# 17_FPGA_B12_B13_B14_B15.net
KiCad netlist of a schematic drawn in Altium Designer
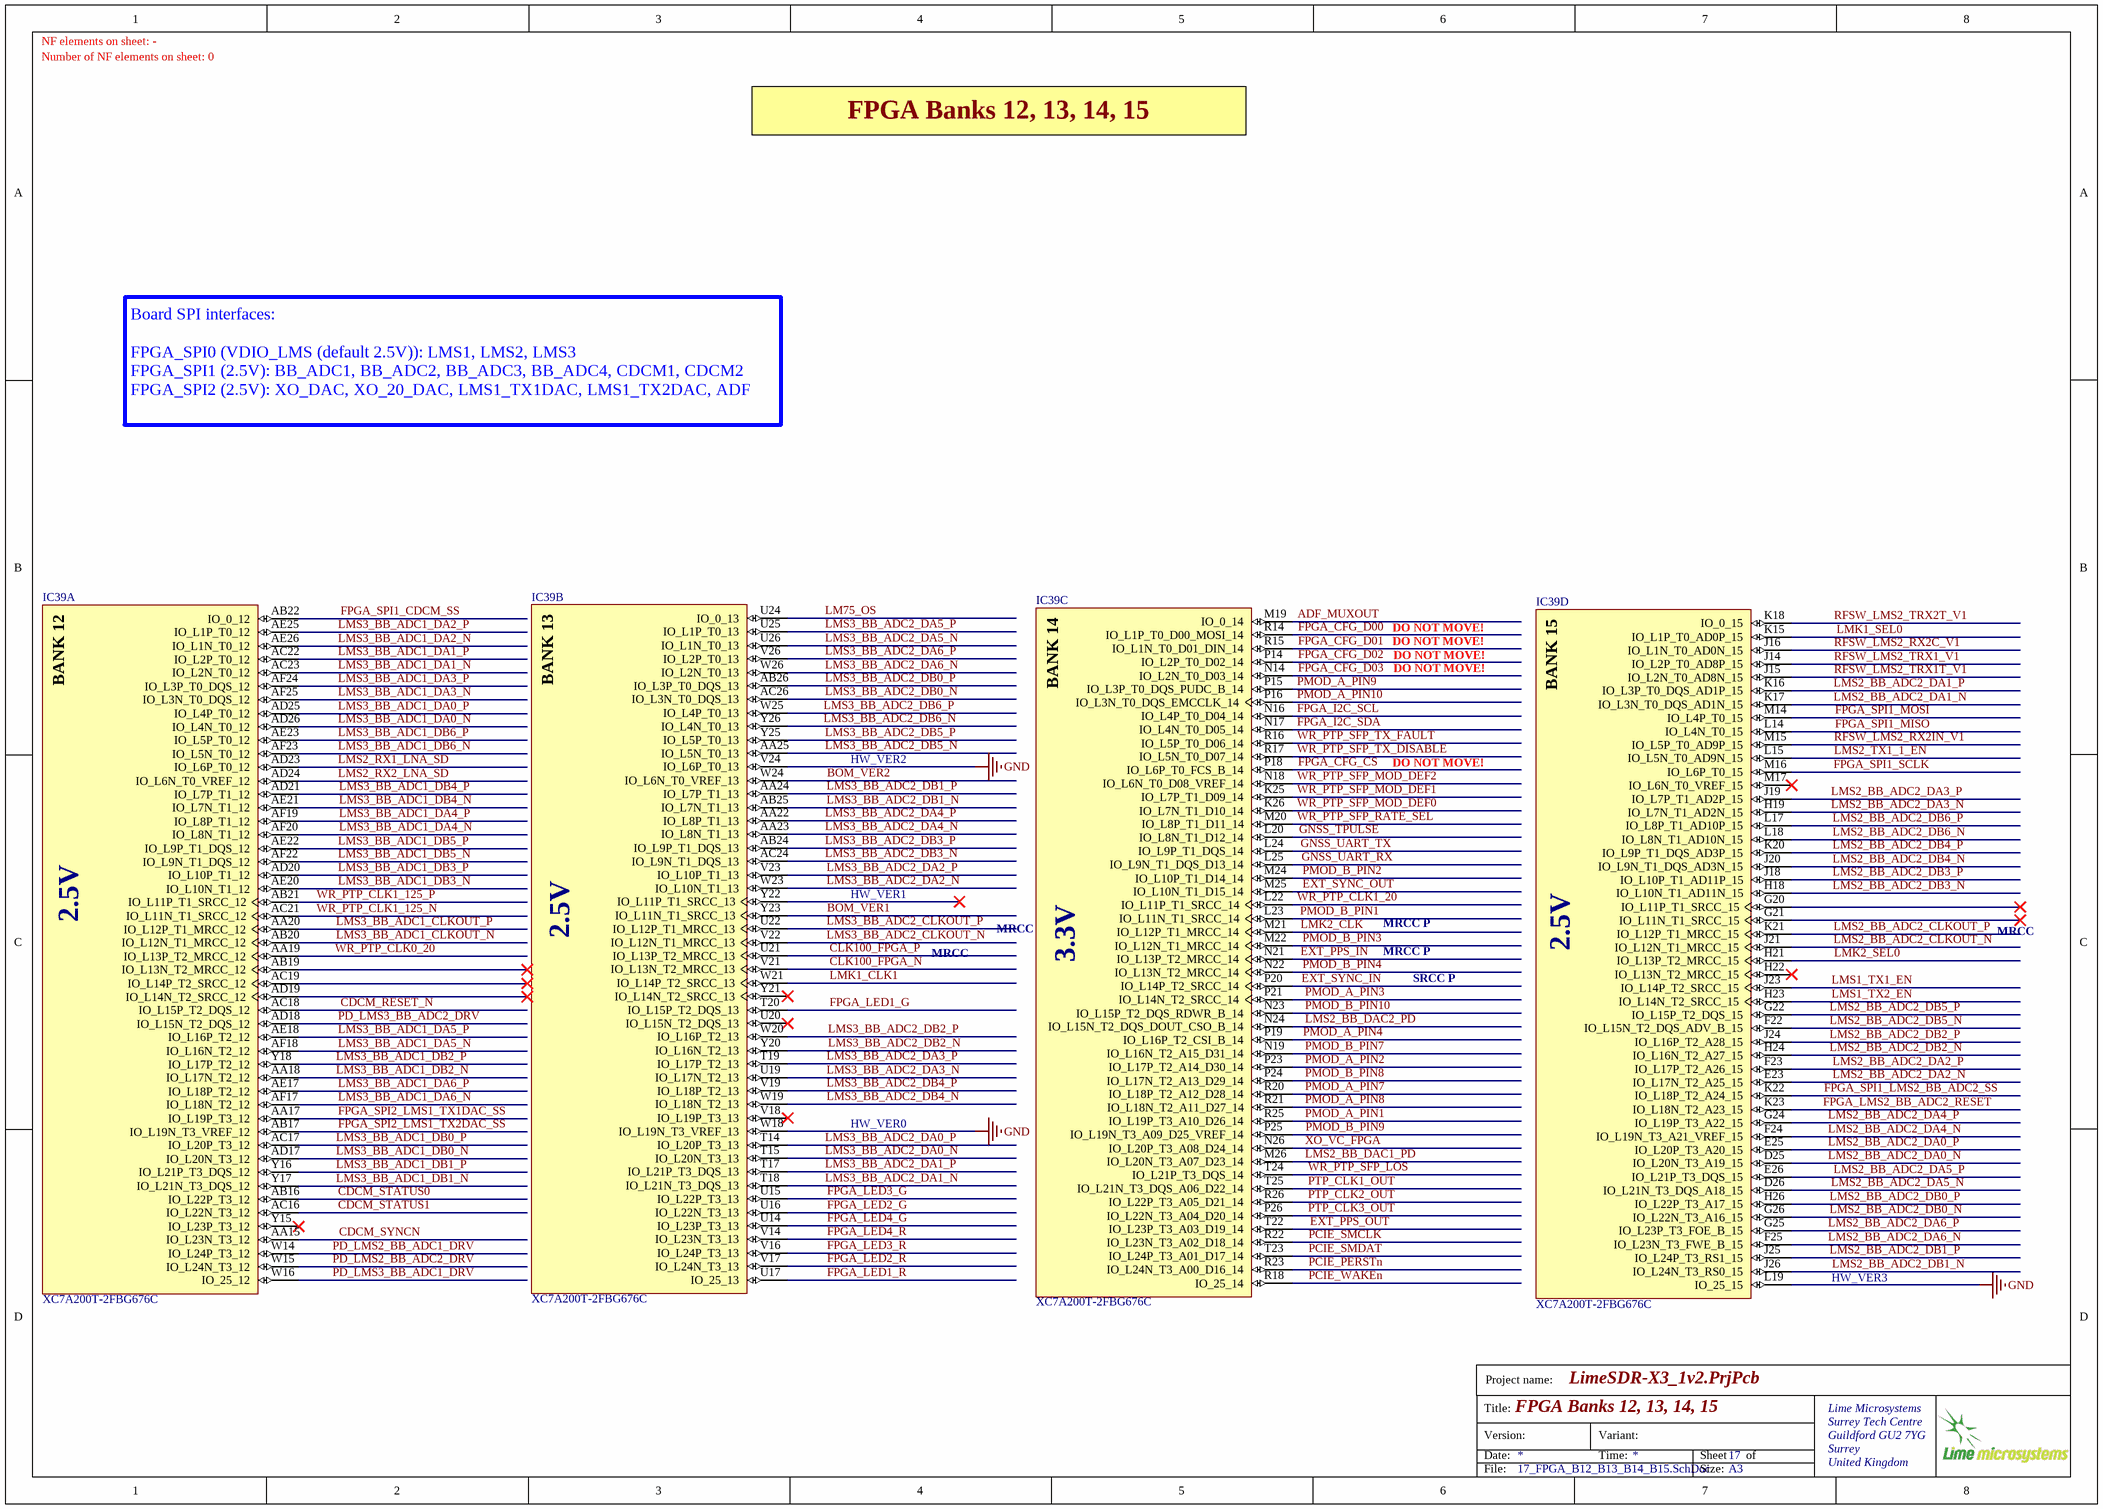
[diagram p0: 17_FPGA_B12_B13_B14_B15.SchDoc]

(export (version "E")
  (design (tool "Eeschema 10.0.6"))
  (components
    (comp (ref "IC39")
      (value "XC7A200T-2FBG676C")
      (footprint "XC7A200T-2FBG676C_FBG676")
      (description "Artix-7 FPGA, 400 User I/Os, 8 GTP, 676-Ball BGA, Speed Grade 2, Commercial Grade, Pb-Free")
      (fields (field (name "MANUFACTURER") "Xilinx"))
      (libsource (lib "") (part "XC7A200T-2FBG676C_3"))
    )
  )
  (nets
    (net (code "1") (name "/ADF_MUXOUT") (class "Default")
      (node (ref "IC39") (pin "M19") (pinfunction "IO_0_14_M19") (pintype "bidirectional"))
    )
    (net (code "2") (name "/BOM_VER1") (class "Default")
      (node (ref "IC39") (pin "Y23") (pinfunction "IO_L11N_T1_SRCC_13_Y23") (pintype "bidirectional"))
    )
    (net (code "3") (name "/BOM_VER2") (class "Default")
      (node (ref "IC39") (pin "W24") (pinfunction "IO_L6N_T0_VREF_13_W24") (pintype "bidirectional"))
    )
    (net (code "4") (name "/CDCM_RESET_N") (class "Default")
      (node (ref "IC39") (pin "AC18") (pinfunction "IO_L15P_T2_DQS_12_AC18") (pintype "bidirectional"))
    )
    (net (code "5") (name "/CDCM_STATUS0") (class "Default")
      (node (ref "IC39") (pin "AB16") (pinfunction "IO_L22P_T3_12_AB16") (pintype "bidirectional"))
    )
    (net (code "6") (name "/CDCM_STATUS1") (class "Default")
      (node (ref "IC39") (pin "AC16") (pinfunction "IO_L22N_T3_12_AC16") (pintype "bidirectional"))
    )
    (net (code "7") (name "/CDCM_SYNCN") (class "Default")
      (node (ref "IC39") (pin "AA15") (pinfunction "IO_L23N_T3_12_AA15") (pintype "bidirectional"))
    )
    (net (code "8") (name "/CLK100_FPGA_N") (class "Default")
      (node (ref "IC39") (pin "V21") (pinfunction "IO_L13N_T2_MRCC_13_V21") (pintype "bidirectional"))
    )
    (net (code "9") (name "/CLK100_FPGA_P") (class "Default")
      (node (ref "IC39") (pin "U21") (pinfunction "IO_L13P_T2_MRCC_13_U21") (pintype "bidirectional"))
    )
    (net (code "10") (name "/EXT_PPS_IN") (class "Default")
      (node (ref "IC39") (pin "N21") (pinfunction "IO_L13P_T2_MRCC_14_N21") (pintype "bidirectional"))
    )
    (net (code "11") (name "/EXT_PPS_OUT") (class "Default")
      (node (ref "IC39") (pin "T22") (pinfunction "IO_L23P_T3_A03_D19_14_T22") (pintype "bidirectional"))
    )
    (net (code "12") (name "/EXT_SYNC_IN") (class "Default")
      (node (ref "IC39") (pin "P20") (pinfunction "IO_L14P_T2_SRCC_14_P20") (pintype "bidirectional"))
    )
    (net (code "13") (name "/EXT_SYNC_OUT") (class "Default")
      (node (ref "IC39") (pin "M25") (pinfunction "IO_L10N_T1_D15_14_M25") (pintype "bidirectional"))
    )
    (net (code "14") (name "/FPGA_CFG_CS") (class "Default")
      (node (ref "IC39") (pin "P18") (pinfunction "IO_L6P_T0_FCS_B_14_P18") (pintype "bidirectional"))
    )
    (net (code "15") (name "/FPGA_CFG_D00") (class "Default")
      (node (ref "IC39") (pin "R14") (pinfunction "IO_L1P_T0_D00_MOSI_14_R14") (pintype "bidirectional"))
    )
    (net (code "16") (name "/FPGA_CFG_D01") (class "Default")
      (node (ref "IC39") (pin "R15") (pinfunction "IO_L1N_T0_D01_DIN_14_R15") (pintype "bidirectional"))
    )
    (net (code "17") (name "/FPGA_CFG_D02") (class "Default")
      (node (ref "IC39") (pin "P14") (pinfunction "IO_L2P_T0_D02_14_P14") (pintype "bidirectional"))
    )
    (net (code "18") (name "/FPGA_CFG_D03") (class "Default")
      (node (ref "IC39") (pin "N14") (pinfunction "IO_L2N_T0_D03_14_N14") (pintype "bidirectional"))
    )
    (net (code "19") (name "/FPGA_I2C_SCL") (class "Default")
      (node (ref "IC39") (pin "N16") (pinfunction "IO_L4P_T0_D04_14_N16") (pintype "bidirectional"))
    )
    (net (code "20") (name "/FPGA_I2C_SDA") (class "Default")
      (node (ref "IC39") (pin "N17") (pinfunction "IO_L4N_T0_D05_14_N17") (pintype "bidirectional"))
    )
    (net (code "21") (name "/FPGA_LED1_G") (class "Default")
      (node (ref "IC39") (pin "T20") (pinfunction "IO_L15P_T2_DQS_13_T20") (pintype "bidirectional"))
    )
    (net (code "22") (name "/FPGA_LED1_R") (class "Default")
      (node (ref "IC39") (pin "U17") (pinfunction "IO_25_13_U17") (pintype "bidirectional"))
    )
    (net (code "23") (name "/FPGA_LED2_G") (class "Default")
      (node (ref "IC39") (pin "U16") (pinfunction "IO_L22N_T3_13_U16") (pintype "bidirectional"))
    )
    (net (code "24") (name "/FPGA_LED2_R") (class "Default")
      (node (ref "IC39") (pin "V17") (pinfunction "IO_L24N_T3_13_V17") (pintype "bidirectional"))
    )
    (net (code "25") (name "/FPGA_LED3_G") (class "Default")
      (node (ref "IC39") (pin "U15") (pinfunction "IO_L22P_T3_13_U15") (pintype "bidirectional"))
    )
    (net (code "26") (name "/FPGA_LED3_R") (class "Default")
      (node (ref "IC39") (pin "V16") (pinfunction "IO_L24P_T3_13_V16") (pintype "bidirectional"))
    )
    (net (code "27") (name "/FPGA_LED4_G") (class "Default")
      (node (ref "IC39") (pin "U14") (pinfunction "IO_L23P_T3_13_U14") (pintype "bidirectional"))
    )
    (net (code "28") (name "/FPGA_LED4_R") (class "Default")
      (node (ref "IC39") (pin "V14") (pinfunction "IO_L23N_T3_13_V14") (pintype "bidirectional"))
    )
    (net (code "29") (name "/FPGA_LMS2_BB_ADC2_RESET") (class "Default")
      (node (ref "IC39") (pin "K23") (pinfunction "IO_L18N_T2_A23_15_K23") (pintype "bidirectional"))
    )
    (net (code "30") (name "/FPGA_SPI1_CDCM_SS") (class "Default")
      (node (ref "IC39") (pin "AB22") (pinfunction "IO_0_12_AB22") (pintype "bidirectional"))
    )
    (net (code "31") (name "/FPGA_SPI1_LMS2_BB_ADC2_SS") (class "Default")
      (node (ref "IC39") (pin "K22") (pinfunction "IO_L18P_T2_A24_15_K22") (pintype "bidirectional"))
    )
    (net (code "32") (name "/FPGA_SPI1_MISO") (class "Default")
      (node (ref "IC39") (pin "L14") (pinfunction "IO_L4N_T0_15_L14") (pintype "bidirectional"))
    )
    (net (code "33") (name "/FPGA_SPI1_MOSI") (class "Default")
      (node (ref "IC39") (pin "M14") (pinfunction "IO_L4P_T0_15_M14") (pintype "bidirectional"))
    )
    (net (code "34") (name "/FPGA_SPI1_SCLK") (class "Default")
      (node (ref "IC39") (pin "M16") (pinfunction "IO_L6P_T0_15_M16") (pintype "bidirectional"))
    )
    (net (code "35") (name "/FPGA_SPI2_LMS1_TX1DAC_SS") (class "Default")
      (node (ref "IC39") (pin "AA17") (pinfunction "IO_L19P_T3_12_AA17") (pintype "bidirectional"))
    )
    (net (code "36") (name "/FPGA_SPI2_LMS1_TX2DAC_SS") (class "Default")
      (node (ref "IC39") (pin "AB17") (pinfunction "IO_L19N_T3_VREF_12_AB17") (pintype "bidirectional"))
    )
    (net (code "37") (name "/GNSS_TPULSE") (class "Default")
      (node (ref "IC39") (pin "L20") (pinfunction "IO_L8N_T1_D12_14_L20") (pintype "bidirectional"))
    )
    (net (code "38") (name "/GNSS_UART_RX") (class "Default")
      (node (ref "IC39") (pin "L25") (pinfunction "IO_L9N_T1_DQS_D13_14_L25") (pintype "bidirectional"))
    )
    (net (code "39") (name "/GNSS_UART_TX") (class "Default")
      (node (ref "IC39") (pin "L24") (pinfunction "IO_L9P_T1_DQS_14_L24") (pintype "bidirectional"))
    )
    (net (code "40") (name "/LM75_OS") (class "Default")
      (node (ref "IC39") (pin "U24") (pinfunction "IO_0_13_U24") (pintype "bidirectional"))
    )
    (net (code "41") (name "/LMK1_CLK1") (class "Default")
      (node (ref "IC39") (pin "W21") (pinfunction "IO_L14P_T2_SRCC_13_W21") (pintype "bidirectional"))
    )
    (net (code "42") (name "/LMK1_SEL0") (class "Default")
      (node (ref "IC39") (pin "K15") (pinfunction "IO_L1P_T0_AD0P_15_K15") (pintype "bidirectional"))
    )
    (net (code "43") (name "/LMK2_CLK") (class "Default")
      (node (ref "IC39") (pin "M21") (pinfunction "IO_L12P_T1_MRCC_14_M21") (pintype "bidirectional"))
    )
    (net (code "44") (name "/LMK2_SEL0") (class "Default")
      (node (ref "IC39") (pin "H21") (pinfunction "IO_L13P_T2_MRCC_15_H21") (pintype "bidirectional"))
    )
    (net (code "45") (name "/LMS1_TX1_EN") (class "Default")
      (node (ref "IC39") (pin "J23") (pinfunction "IO_L14P_T2_SRCC_15_J23") (pintype "bidirectional"))
    )
    (net (code "46") (name "/LMS1_TX2_EN") (class "Default")
      (node (ref "IC39") (pin "H23") (pinfunction "IO_L14N_T2_SRCC_15_H23") (pintype "bidirectional"))
    )
    (net (code "47") (name "/LMS2_BB_ADC2_CLKOUT_N") (class "Default")
      (node (ref "IC39") (pin "J21") (pinfunction "IO_L12N_T1_MRCC_15_J21") (pintype "bidirectional"))
    )
    (net (code "48") (name "/LMS2_BB_ADC2_CLKOUT_P") (class "Default")
      (node (ref "IC39") (pin "K21") (pinfunction "IO_L12P_T1_MRCC_15_K21") (pintype "bidirectional"))
    )
    (net (code "49") (name "/LMS2_BB_ADC2_DA0_N") (class "Default")
      (node (ref "IC39") (pin "D25") (pinfunction "IO_L20N_T3_A19_15_D25") (pintype "bidirectional"))
    )
    (net (code "50") (name "/LMS2_BB_ADC2_DA0_P") (class "Default")
      (node (ref "IC39") (pin "E25") (pinfunction "IO_L20P_T3_A20_15_E25") (pintype "bidirectional"))
    )
    (net (code "51") (name "/LMS2_BB_ADC2_DA1_N") (class "Default")
      (node (ref "IC39") (pin "K17") (pinfunction "IO_L3N_T0_DQS_AD1N_15_K17") (pintype "bidirectional"))
    )
    (net (code "52") (name "/LMS2_BB_ADC2_DA1_P") (class "Default")
      (node (ref "IC39") (pin "K16") (pinfunction "IO_L3P_T0_DQS_AD1P_15_K16") (pintype "bidirectional"))
    )
    (net (code "53") (name "/LMS2_BB_ADC2_DA2_N") (class "Default")
      (node (ref "IC39") (pin "E23") (pinfunction "IO_L17N_T2_A25_15_E23") (pintype "bidirectional"))
    )
    (net (code "54") (name "/LMS2_BB_ADC2_DA2_P") (class "Default")
      (node (ref "IC39") (pin "F23") (pinfunction "IO_L17P_T2_A26_15_F23") (pintype "bidirectional"))
    )
    (net (code "55") (name "/LMS2_BB_ADC2_DA3_N") (class "Default")
      (node (ref "IC39") (pin "H19") (pinfunction "IO_L7N_T1_AD2N_15_H19") (pintype "bidirectional"))
    )
    (net (code "56") (name "/LMS2_BB_ADC2_DA3_P") (class "Default")
      (node (ref "IC39") (pin "J19") (pinfunction "IO_L7P_T1_AD2P_15_J19") (pintype "bidirectional"))
    )
    (net (code "57") (name "/LMS2_BB_ADC2_DA4_N") (class "Default")
      (node (ref "IC39") (pin "F24") (pinfunction "IO_L19N_T3_A21_VREF_15_F24") (pintype "bidirectional"))
    )
    (net (code "58") (name "/LMS2_BB_ADC2_DA4_P") (class "Default")
      (node (ref "IC39") (pin "G24") (pinfunction "IO_L19P_T3_A22_15_G24") (pintype "bidirectional"))
    )
    (net (code "59") (name "/LMS2_BB_ADC2_DA5_N") (class "Default")
      (node (ref "IC39") (pin "D26") (pinfunction "IO_L21N_T3_DQS_A18_15_D26") (pintype "bidirectional"))
    )
    (net (code "60") (name "/LMS2_BB_ADC2_DA5_P") (class "Default")
      (node (ref "IC39") (pin "E26") (pinfunction "IO_L21P_T3_DQS_15_E26") (pintype "bidirectional"))
    )
    (net (code "61") (name "/LMS2_BB_ADC2_DA6_N") (class "Default")
      (node (ref "IC39") (pin "F25") (pinfunction "IO_L23N_T3_FWE_B_15_F25") (pintype "bidirectional"))
    )
    (net (code "62") (name "/LMS2_BB_ADC2_DA6_P") (class "Default")
      (node (ref "IC39") (pin "G25") (pinfunction "IO_L23P_T3_FOE_B_15_G25") (pintype "bidirectional"))
    )
    (net (code "63") (name "/LMS2_BB_ADC2_DB0_N") (class "Default")
      (node (ref "IC39") (pin "G26") (pinfunction "IO_L22N_T3_A16_15_G26") (pintype "bidirectional"))
    )
    (net (code "64") (name "/LMS2_BB_ADC2_DB0_P") (class "Default")
      (node (ref "IC39") (pin "H26") (pinfunction "IO_L22P_T3_A17_15_H26") (pintype "bidirectional"))
    )
    (net (code "65") (name "/LMS2_BB_ADC2_DB1_N") (class "Default")
      (node (ref "IC39") (pin "J26") (pinfunction "IO_L24N_T3_RS0_15_J26") (pintype "bidirectional"))
    )
    (net (code "66") (name "/LMS2_BB_ADC2_DB1_P") (class "Default")
      (node (ref "IC39") (pin "J25") (pinfunction "IO_L24P_T3_RS1_15_J25") (pintype "bidirectional"))
    )
    (net (code "67") (name "/LMS2_BB_ADC2_DB2_N") (class "Default")
      (node (ref "IC39") (pin "H24") (pinfunction "IO_L16N_T2_A27_15_H24") (pintype "bidirectional"))
    )
    (net (code "68") (name "/LMS2_BB_ADC2_DB2_P") (class "Default")
      (node (ref "IC39") (pin "J24") (pinfunction "IO_L16P_T2_A28_15_J24") (pintype "bidirectional"))
    )
    (net (code "69") (name "/LMS2_BB_ADC2_DB3_N") (class "Default")
      (node (ref "IC39") (pin "H18") (pinfunction "IO_L10N_T1_AD11N_15_H18") (pintype "bidirectional"))
    )
    (net (code "70") (name "/LMS2_BB_ADC2_DB3_P") (class "Default")
      (node (ref "IC39") (pin "J18") (pinfunction "IO_L10P_T1_AD11P_15_J18") (pintype "bidirectional"))
    )
    (net (code "71") (name "/LMS2_BB_ADC2_DB4_N") (class "Default")
      (node (ref "IC39") (pin "J20") (pinfunction "IO_L9N_T1_DQS_AD3N_15_J20") (pintype "bidirectional"))
    )
    (net (code "72") (name "/LMS2_BB_ADC2_DB4_P") (class "Default")
      (node (ref "IC39") (pin "K20") (pinfunction "IO_L9P_T1_DQS_AD3P_15_K20") (pintype "bidirectional"))
    )
    (net (code "73") (name "/LMS2_BB_ADC2_DB5_N") (class "Default")
      (node (ref "IC39") (pin "F22") (pinfunction "IO_L15N_T2_DQS_ADV_B_15_F22") (pintype "bidirectional"))
    )
    (net (code "74") (name "/LMS2_BB_ADC2_DB5_P") (class "Default")
      (node (ref "IC39") (pin "G22") (pinfunction "IO_L15P_T2_DQS_15_G22") (pintype "bidirectional"))
    )
    (net (code "75") (name "/LMS2_BB_ADC2_DB6_N") (class "Default")
      (node (ref "IC39") (pin "L18") (pinfunction "IO_L8N_T1_AD10N_15_L18") (pintype "bidirectional"))
    )
    (net (code "76") (name "/LMS2_BB_ADC2_DB6_P") (class "Default")
      (node (ref "IC39") (pin "L17") (pinfunction "IO_L8P_T1_AD10P_15_L17") (pintype "bidirectional"))
    )
    (net (code "77") (name "/LMS2_BB_DAC1_PD") (class "Default")
      (node (ref "IC39") (pin "M26") (pinfunction "IO_L20N_T3_A07_D23_14_M26") (pintype "bidirectional"))
    )
    (net (code "78") (name "/LMS2_BB_DAC2_PD") (class "Default")
      (node (ref "IC39") (pin "N24") (pinfunction "IO_L15N_T2_DQS_DOUT_CSO_B_14_N24") (pintype "bidirectional"))
    )
    (net (code "79") (name "/LMS2_RX1_LNA_SD") (class "Default")
      (node (ref "IC39") (pin "AD23") (pinfunction "IO_L6P_T0_12_AD23") (pintype "bidirectional"))
    )
    (net (code "80") (name "/LMS2_RX2_LNA_SD") (class "Default")
      (node (ref "IC39") (pin "AD24") (pinfunction "IO_L6N_T0_VREF_12_AD24") (pintype "bidirectional"))
    )
    (net (code "81") (name "/LMS2_TX1_1_EN") (class "Default")
      (node (ref "IC39") (pin "L15") (pinfunction "IO_L5N_T0_AD9N_15_L15") (pintype "bidirectional"))
    )
    (net (code "82") (name "/LMS3_BB_ADC1_CLKOUT_N") (class "Default")
      (node (ref "IC39") (pin "AB20") (pinfunction "IO_L12N_T1_MRCC_12_AB20") (pintype "bidirectional"))
    )
    (net (code "83") (name "/LMS3_BB_ADC1_CLKOUT_P") (class "Default")
      (node (ref "IC39") (pin "AA20") (pinfunction "IO_L12P_T1_MRCC_12_AA20") (pintype "bidirectional"))
    )
    (net (code "84") (name "/LMS3_BB_ADC1_DA0_N") (class "Default")
      (node (ref "IC39") (pin "AD26") (pinfunction "IO_L4N_T0_12_AD26") (pintype "bidirectional"))
    )
    (net (code "85") (name "/LMS3_BB_ADC1_DA0_P") (class "Default")
      (node (ref "IC39") (pin "AD25") (pinfunction "IO_L4P_T0_12_AD25") (pintype "bidirectional"))
    )
    (net (code "86") (name "/LMS3_BB_ADC1_DA1_N") (class "Default")
      (node (ref "IC39") (pin "AC23") (pinfunction "IO_L2N_T0_12_AC23") (pintype "bidirectional"))
    )
    (net (code "87") (name "/LMS3_BB_ADC1_DA1_P") (class "Default")
      (node (ref "IC39") (pin "AC22") (pinfunction "IO_L2P_T0_12_AC22") (pintype "bidirectional"))
    )
    (net (code "88") (name "/LMS3_BB_ADC1_DA2_N") (class "Default")
      (node (ref "IC39") (pin "AE26") (pinfunction "IO_L1N_T0_12_AE26") (pintype "bidirectional"))
    )
    (net (code "89") (name "/LMS3_BB_ADC1_DA2_P") (class "Default")
      (node (ref "IC39") (pin "AE25") (pinfunction "IO_L1P_T0_12_AE25") (pintype "bidirectional"))
    )
    (net (code "90") (name "/LMS3_BB_ADC1_DA3_N") (class "Default")
      (node (ref "IC39") (pin "AF25") (pinfunction "IO_L3N_T0_DQS_12_AF25") (pintype "bidirectional"))
    )
    (net (code "91") (name "/LMS3_BB_ADC1_DA3_P") (class "Default")
      (node (ref "IC39") (pin "AF24") (pinfunction "IO_L3P_T0_DQS_12_AF24") (pintype "bidirectional"))
    )
    (net (code "92") (name "/LMS3_BB_ADC1_DA4_N") (class "Default")
      (node (ref "IC39") (pin "AF20") (pinfunction "IO_L8N_T1_12_AF20") (pintype "bidirectional"))
    )
    (net (code "93") (name "/LMS3_BB_ADC1_DA4_P") (class "Default")
      (node (ref "IC39") (pin "AF19") (pinfunction "IO_L8P_T1_12_AF19") (pintype "bidirectional"))
    )
    (net (code "94") (name "/LMS3_BB_ADC1_DA5_N") (class "Default")
      (node (ref "IC39") (pin "AF18") (pinfunction "IO_L16N_T2_12_AF18") (pintype "bidirectional"))
    )
    (net (code "95") (name "/LMS3_BB_ADC1_DA5_P") (class "Default")
      (node (ref "IC39") (pin "AE18") (pinfunction "IO_L16P_T2_12_AE18") (pintype "bidirectional"))
    )
    (net (code "96") (name "/LMS3_BB_ADC1_DA6_N") (class "Default")
      (node (ref "IC39") (pin "AF17") (pinfunction "IO_L18N_T2_12_AF17") (pintype "bidirectional"))
    )
    (net (code "97") (name "/LMS3_BB_ADC1_DA6_P") (class "Default")
      (node (ref "IC39") (pin "AE17") (pinfunction "IO_L18P_T2_12_AE17") (pintype "bidirectional"))
    )
    (net (code "98") (name "/LMS3_BB_ADC1_DB0_N") (class "Default")
      (node (ref "IC39") (pin "AD17") (pinfunction "IO_L20N_T3_12_AD17") (pintype "bidirectional"))
    )
    (net (code "99") (name "/LMS3_BB_ADC1_DB0_P") (class "Default")
      (node (ref "IC39") (pin "AC17") (pinfunction "IO_L20P_T3_12_AC17") (pintype "bidirectional"))
    )
    (net (code "100") (name "/LMS3_BB_ADC1_DB1_N") (class "Default")
      (node (ref "IC39") (pin "Y17") (pinfunction "IO_L21N_T3_DQS_12_Y17") (pintype "bidirectional"))
    )
    (net (code "101") (name "/LMS3_BB_ADC1_DB1_P") (class "Default")
      (node (ref "IC39") (pin "Y16") (pinfunction "IO_L21P_T3_DQS_12_Y16") (pintype "bidirectional"))
    )
    (net (code "102") (name "/LMS3_BB_ADC1_DB2_N") (class "Default")
      (node (ref "IC39") (pin "AA18") (pinfunction "IO_L17N_T2_12_AA18") (pintype "bidirectional"))
    )
    (net (code "103") (name "/LMS3_BB_ADC1_DB2_P") (class "Default")
      (node (ref "IC39") (pin "Y18") (pinfunction "IO_L17P_T2_12_Y18") (pintype "bidirectional"))
    )
    (net (code "104") (name "/LMS3_BB_ADC1_DB3_N") (class "Default")
      (node (ref "IC39") (pin "AE20") (pinfunction "IO_L10N_T1_12_AE20") (pintype "bidirectional"))
    )
    (net (code "105") (name "/LMS3_BB_ADC1_DB3_P") (class "Default")
      (node (ref "IC39") (pin "AD20") (pinfunction "IO_L10P_T1_12_AD20") (pintype "bidirectional"))
    )
    (net (code "106") (name "/LMS3_BB_ADC1_DB4_N") (class "Default")
      (node (ref "IC39") (pin "AE21") (pinfunction "IO_L7N_T1_12_AE21") (pintype "bidirectional"))
    )
    (net (code "107") (name "/LMS3_BB_ADC1_DB4_P") (class "Default")
      (node (ref "IC39") (pin "AD21") (pinfunction "IO_L7P_T1_12_AD21") (pintype "bidirectional"))
    )
    (net (code "108") (name "/LMS3_BB_ADC1_DB5_N") (class "Default")
      (node (ref "IC39") (pin "AF22") (pinfunction "IO_L9N_T1_DQS_12_AF22") (pintype "bidirectional"))
    )
    (net (code "109") (name "/LMS3_BB_ADC1_DB5_P") (class "Default")
      (node (ref "IC39") (pin "AE22") (pinfunction "IO_L9P_T1_DQS_12_AE22") (pintype "bidirectional"))
    )
    (net (code "110") (name "/LMS3_BB_ADC1_DB6_N") (class "Default")
      (node (ref "IC39") (pin "AF23") (pinfunction "IO_L5N_T0_12_AF23") (pintype "bidirectional"))
    )
    (net (code "111") (name "/LMS3_BB_ADC1_DB6_P") (class "Default")
      (node (ref "IC39") (pin "AE23") (pinfunction "IO_L5P_T0_12_AE23") (pintype "bidirectional"))
    )
    (net (code "112") (name "/LMS3_BB_ADC2_CLKOUT_N") (class "Default")
      (node (ref "IC39") (pin "V22") (pinfunction "IO_L12N_T1_MRCC_13_V22") (pintype "bidirectional"))
    )
    (net (code "113") (name "/LMS3_BB_ADC2_CLKOUT_P") (class "Default")
      (node (ref "IC39") (pin "U22") (pinfunction "IO_L12P_T1_MRCC_13_U22") (pintype "bidirectional"))
    )
    (net (code "114") (name "/LMS3_BB_ADC2_DA0_N") (class "Default")
      (node (ref "IC39") (pin "T15") (pinfunction "IO_L20N_T3_13_T15") (pintype "bidirectional"))
    )
    (net (code "115") (name "/LMS3_BB_ADC2_DA0_P") (class "Default")
      (node (ref "IC39") (pin "T14") (pinfunction "IO_L20P_T3_13_T14") (pintype "bidirectional"))
    )
    (net (code "116") (name "/LMS3_BB_ADC2_DA1_N") (class "Default")
      (node (ref "IC39") (pin "T18") (pinfunction "IO_L21N_T3_DQS_13_T18") (pintype "bidirectional"))
    )
    (net (code "117") (name "/LMS3_BB_ADC2_DA1_P") (class "Default")
      (node (ref "IC39") (pin "T17") (pinfunction "IO_L21P_T3_DQS_13_T17") (pintype "bidirectional"))
    )
    (net (code "118") (name "/LMS3_BB_ADC2_DA2_N") (class "Default")
      (node (ref "IC39") (pin "W23") (pinfunction "IO_L10N_T1_13_W23") (pintype "bidirectional"))
    )
    (net (code "119") (name "/LMS3_BB_ADC2_DA2_P") (class "Default")
      (node (ref "IC39") (pin "V23") (pinfunction "IO_L10P_T1_13_V23") (pintype "bidirectional"))
    )
    (net (code "120") (name "/LMS3_BB_ADC2_DA3_N") (class "Default")
      (node (ref "IC39") (pin "U19") (pinfunction "IO_L17N_T2_13_U19") (pintype "bidirectional"))
    )
    (net (code "121") (name "/LMS3_BB_ADC2_DA3_P") (class "Default")
      (node (ref "IC39") (pin "T19") (pinfunction "IO_L17P_T2_13_T19") (pintype "bidirectional"))
    )
    (net (code "122") (name "/LMS3_BB_ADC2_DA4_N") (class "Default")
      (node (ref "IC39") (pin "AA23") (pinfunction "IO_L8N_T1_13_AA23") (pintype "bidirectional"))
    )
    (net (code "123") (name "/LMS3_BB_ADC2_DA4_P") (class "Default")
      (node (ref "IC39") (pin "AA22") (pinfunction "IO_L8P_T1_13_AA22") (pintype "bidirectional"))
    )
    (net (code "124") (name "/LMS3_BB_ADC2_DA5_N") (class "Default")
      (node (ref "IC39") (pin "U26") (pinfunction "IO_L1N_T0_13_U26") (pintype "bidirectional"))
    )
    (net (code "125") (name "/LMS3_BB_ADC2_DA5_P") (class "Default")
      (node (ref "IC39") (pin "U25") (pinfunction "IO_L1P_T0_13_U25") (pintype "bidirectional"))
    )
    (net (code "126") (name "/LMS3_BB_ADC2_DA6_N") (class "Default")
      (node (ref "IC39") (pin "W26") (pinfunction "IO_L2N_T0_13_W26") (pintype "bidirectional"))
    )
    (net (code "127") (name "/LMS3_BB_ADC2_DA6_P") (class "Default")
      (node (ref "IC39") (pin "V26") (pinfunction "IO_L2P_T0_13_V26") (pintype "bidirectional"))
    )
    (net (code "128") (name "/LMS3_BB_ADC2_DB0_N") (class "Default")
      (node (ref "IC39") (pin "AC26") (pinfunction "IO_L3N_T0_DQS_13_AC26") (pintype "bidirectional"))
    )
    (net (code "129") (name "/LMS3_BB_ADC2_DB0_P") (class "Default")
      (node (ref "IC39") (pin "AB26") (pinfunction "IO_L3P_T0_DQS_13_AB26") (pintype "bidirectional"))
    )
    (net (code "130") (name "/LMS3_BB_ADC2_DB1_N") (class "Default")
      (node (ref "IC39") (pin "AB25") (pinfunction "IO_L7N_T1_13_AB25") (pintype "bidirectional"))
    )
    (net (code "131") (name "/LMS3_BB_ADC2_DB1_P") (class "Default")
      (node (ref "IC39") (pin "AA24") (pinfunction "IO_L7P_T1_13_AA24") (pintype "bidirectional"))
    )
    (net (code "132") (name "/LMS3_BB_ADC2_DB2_N") (class "Default")
      (node (ref "IC39") (pin "Y20") (pinfunction "IO_L16N_T2_13_Y20") (pintype "bidirectional"))
    )
    (net (code "133") (name "/LMS3_BB_ADC2_DB2_P") (class "Default")
      (node (ref "IC39") (pin "W20") (pinfunction "IO_L16P_T2_13_W20") (pintype "bidirectional"))
    )
    (net (code "134") (name "/LMS3_BB_ADC2_DB3_N") (class "Default")
      (node (ref "IC39") (pin "AC24") (pinfunction "IO_L9N_T1_DQS_13_AC24") (pintype "bidirectional"))
    )
    (net (code "135") (name "/LMS3_BB_ADC2_DB3_P") (class "Default")
      (node (ref "IC39") (pin "AB24") (pinfunction "IO_L9P_T1_DQS_13_AB24") (pintype "bidirectional"))
    )
    (net (code "136") (name "/LMS3_BB_ADC2_DB4_N") (class "Default")
      (node (ref "IC39") (pin "W19") (pinfunction "IO_L18N_T2_13_W19") (pintype "bidirectional"))
    )
    (net (code "137") (name "/LMS3_BB_ADC2_DB4_P") (class "Default")
      (node (ref "IC39") (pin "V19") (pinfunction "IO_L18P_T2_13_V19") (pintype "bidirectional"))
    )
    (net (code "138") (name "/LMS3_BB_ADC2_DB5_N") (class "Default")
      (node (ref "IC39") (pin "AA25") (pinfunction "IO_L5N_T0_13_AA25") (pintype "bidirectional"))
    )
    (net (code "139") (name "/LMS3_BB_ADC2_DB5_P") (class "Default")
      (node (ref "IC39") (pin "Y25") (pinfunction "IO_L5P_T0_13_Y25") (pintype "bidirectional"))
    )
    (net (code "140") (name "/LMS3_BB_ADC2_DB6_N") (class "Default")
      (node (ref "IC39") (pin "Y26") (pinfunction "IO_L4N_T0_13_Y26") (pintype "bidirectional"))
    )
    (net (code "141") (name "/LMS3_BB_ADC2_DB6_P") (class "Default")
      (node (ref "IC39") (pin "W25") (pinfunction "IO_L4P_T0_13_W25") (pintype "bidirectional"))
    )
    (net (code "142") (name "/PCIE_PERSTn") (class "Default")
      (node (ref "IC39") (pin "R23") (pinfunction "IO_L24N_T3_A00_D16_14_R23") (pintype "bidirectional"))
    )
    (net (code "143") (name "/PCIE_SMCLK") (class "Default")
      (node (ref "IC39") (pin "R22") (pinfunction "IO_L23N_T3_A02_D18_14_R22") (pintype "bidirectional"))
    )
    (net (code "144") (name "/PCIE_SMDAT") (class "Default")
      (node (ref "IC39") (pin "T23") (pinfunction "IO_L24P_T3_A01_D17_14_T23") (pintype "bidirectional"))
    )
    (net (code "145") (name "/PCIE_WAKEn") (class "Default")
      (node (ref "IC39") (pin "R18") (pinfunction "IO_25_14_R18") (pintype "bidirectional"))
    )
    (net (code "146") (name "/PD_LMS2_BB_ADC1_DRV") (class "Default")
      (node (ref "IC39") (pin "W14") (pinfunction "IO_L24P_T3_12_W14") (pintype "bidirectional"))
    )
    (net (code "147") (name "/PD_LMS2_BB_ADC2_DRV") (class "Default")
      (node (ref "IC39") (pin "W15") (pinfunction "IO_L24N_T3_12_W15") (pintype "bidirectional"))
    )
    (net (code "148") (name "/PD_LMS3_BB_ADC1_DRV") (class "Default")
      (node (ref "IC39") (pin "W16") (pinfunction "IO_25_12_W16") (pintype "bidirectional"))
    )
    (net (code "149") (name "/PD_LMS3_BB_ADC2_DRV") (class "Default")
      (node (ref "IC39") (pin "AD18") (pinfunction "IO_L15N_T2_DQS_12_AD18") (pintype "bidirectional"))
    )
    (net (code "150") (name "/PMOD_A_PIN1") (class "Default")
      (node (ref "IC39") (pin "R25") (pinfunction "IO_L19P_T3_A10_D26_14_R25") (pintype "bidirectional"))
    )
    (net (code "151") (name "/PMOD_A_PIN2") (class "Default")
      (node (ref "IC39") (pin "P23") (pinfunction "IO_L17P_T2_A14_D30_14_P23") (pintype "bidirectional"))
    )
    (net (code "152") (name "/PMOD_A_PIN3") (class "Default")
      (node (ref "IC39") (pin "P21") (pinfunction "IO_L14N_T2_SRCC_14_P21") (pintype "bidirectional"))
    )
    (net (code "153") (name "/PMOD_A_PIN4") (class "Default")
      (node (ref "IC39") (pin "P19") (pinfunction "IO_L16P_T2_CSI_B_14_P19") (pintype "bidirectional"))
    )
    (net (code "154") (name "/PMOD_A_PIN7") (class "Default")
      (node (ref "IC39") (pin "R20") (pinfunction "IO_L18P_T2_A12_D28_14_R20") (pintype "bidirectional"))
    )
    (net (code "155") (name "/PMOD_A_PIN8") (class "Default")
      (node (ref "IC39") (pin "R21") (pinfunction "IO_L18N_T2_A11_D27_14_R21") (pintype "bidirectional"))
    )
    (net (code "156") (name "/PMOD_A_PIN9") (class "Default")
      (node (ref "IC39") (pin "P15") (pinfunction "IO_L3P_T0_DQS_PUDC_B_14_P15") (pintype "bidirectional"))
    )
    (net (code "157") (name "/PMOD_A_PIN10") (class "Default")
      (node (ref "IC39") (pin "P16") (pinfunction "IO_L3N_T0_DQS_EMCCLK_14_P16") (pintype "bidirectional"))
    )
    (net (code "158") (name "/PMOD_B_PIN1") (class "Default")
      (node (ref "IC39") (pin "L23") (pinfunction "IO_L11N_T1_SRCC_14_L23") (pintype "bidirectional"))
    )
    (net (code "159") (name "/PMOD_B_PIN2") (class "Default")
      (node (ref "IC39") (pin "M24") (pinfunction "IO_L10P_T1_D14_14_M24") (pintype "bidirectional"))
    )
    (net (code "160") (name "/PMOD_B_PIN3") (class "Default")
      (node (ref "IC39") (pin "M22") (pinfunction "IO_L12N_T1_MRCC_14_M22") (pintype "bidirectional"))
    )
    (net (code "161") (name "/PMOD_B_PIN4") (class "Default")
      (node (ref "IC39") (pin "N22") (pinfunction "IO_L13N_T2_MRCC_14_N22") (pintype "bidirectional"))
    )
    (net (code "162") (name "/PMOD_B_PIN7") (class "Default")
      (node (ref "IC39") (pin "N19") (pinfunction "IO_L16N_T2_A15_D31_14_N19") (pintype "bidirectional"))
    )
    (net (code "163") (name "/PMOD_B_PIN8") (class "Default")
      (node (ref "IC39") (pin "P24") (pinfunction "IO_L17N_T2_A13_D29_14_P24") (pintype "bidirectional"))
    )
    (net (code "164") (name "/PMOD_B_PIN9") (class "Default")
      (node (ref "IC39") (pin "P25") (pinfunction "IO_L19N_T3_A09_D25_VREF_14_P25") (pintype "bidirectional"))
    )
    (net (code "165") (name "/PMOD_B_PIN10") (class "Default")
      (node (ref "IC39") (pin "N23") (pinfunction "IO_L15P_T2_DQS_RDWR_B_14_N23") (pintype "bidirectional"))
    )
    (net (code "166") (name "/PTP_CLK1_OUT") (class "Default")
      (node (ref "IC39") (pin "T25") (pinfunction "IO_L21N_T3_DQS_A06_D22_14_T25") (pintype "bidirectional"))
    )
    (net (code "167") (name "/PTP_CLK2_OUT") (class "Default")
      (node (ref "IC39") (pin "R26") (pinfunction "IO_L22P_T3_A05_D21_14_R26") (pintype "bidirectional"))
    )
    (net (code "168") (name "/PTP_CLK3_OUT") (class "Default")
      (node (ref "IC39") (pin "P26") (pinfunction "IO_L22N_T3_A04_D20_14_P26") (pintype "bidirectional"))
    )
    (net (code "169") (name "/RFSW_LMS2_RX2C_V1") (class "Default")
      (node (ref "IC39") (pin "J16") (pinfunction "IO_L1N_T0_AD0N_15_J16") (pintype "bidirectional"))
    )
    (net (code "170") (name "/RFSW_LMS2_RX2IN_V1") (class "Default")
      (node (ref "IC39") (pin "M15") (pinfunction "IO_L5P_T0_AD9P_15_M15") (pintype "bidirectional"))
    )
    (net (code "171") (name "/RFSW_LMS2_TRX1T_V1") (class "Default")
      (node (ref "IC39") (pin "J15") (pinfunction "IO_L2N_T0_AD8N_15_J15") (pintype "bidirectional"))
    )
    (net (code "172") (name "/RFSW_LMS2_TRX1_V1") (class "Default")
      (node (ref "IC39") (pin "J14") (pinfunction "IO_L2P_T0_AD8P_15_J14") (pintype "bidirectional"))
    )
    (net (code "173") (name "/RFSW_LMS2_TRX2T_V1") (class "Default")
      (node (ref "IC39") (pin "K18") (pinfunction "IO_0_15_K18") (pintype "bidirectional"))
    )
    (net (code "174") (name "/WR_PTP_CLK0_20") (class "Default")
      (node (ref "IC39") (pin "AA19") (pinfunction "IO_L13P_T2_MRCC_12_AA19") (pintype "bidirectional"))
    )
    (net (code "175") (name "/WR_PTP_CLK1_20") (class "Default")
      (node (ref "IC39") (pin "L22") (pinfunction "IO_L11P_T1_SRCC_14_L22") (pintype "bidirectional"))
    )
    (net (code "176") (name "/WR_PTP_CLK1_125_N") (class "Default")
      (node (ref "IC39") (pin "AC21") (pinfunction "IO_L11N_T1_SRCC_12_AC21") (pintype "bidirectional"))
    )
    (net (code "177") (name "/WR_PTP_CLK1_125_P") (class "Default")
      (node (ref "IC39") (pin "AB21") (pinfunction "IO_L11P_T1_SRCC_12_AB21") (pintype "bidirectional"))
    )
    (net (code "178") (name "/WR_PTP_SFP_LOS") (class "Default")
      (node (ref "IC39") (pin "T24") (pinfunction "IO_L21P_T3_DQS_14_T24") (pintype "bidirectional"))
    )
    (net (code "179") (name "/WR_PTP_SFP_MOD_DEF0") (class "Default")
      (node (ref "IC39") (pin "K26") (pinfunction "IO_L7N_T1_D10_14_K26") (pintype "bidirectional"))
    )
    (net (code "180") (name "/WR_PTP_SFP_MOD_DEF1") (class "Default")
      (node (ref "IC39") (pin "K25") (pinfunction "IO_L7P_T1_D09_14_K25") (pintype "bidirectional"))
    )
    (net (code "181") (name "/WR_PTP_SFP_MOD_DEF2") (class "Default")
      (node (ref "IC39") (pin "N18") (pinfunction "IO_L6N_T0_D08_VREF_14_N18") (pintype "bidirectional"))
    )
    (net (code "182") (name "/WR_PTP_SFP_RATE_SEL") (class "Default")
      (node (ref "IC39") (pin "M20") (pinfunction "IO_L8P_T1_D11_14_M20") (pintype "bidirectional"))
    )
    (net (code "183") (name "/WR_PTP_SFP_TX_DISABLE") (class "Default")
      (node (ref "IC39") (pin "R17") (pinfunction "IO_L5N_T0_D07_14_R17") (pintype "bidirectional"))
    )
    (net (code "184") (name "/WR_PTP_SFP_TX_FAULT") (class "Default")
      (node (ref "IC39") (pin "R16") (pinfunction "IO_L5P_T0_D06_14_R16") (pintype "bidirectional"))
    )
    (net (code "185") (name "/XO_VC_FPGA") (class "Default")
      (node (ref "IC39") (pin "N26") (pinfunction "IO_L20P_T3_A08_D24_14_N26") (pintype "bidirectional"))
    )
    (net (code "186") (name "GND") (class "Default")
      (node (ref "IC39") (pin "L19") (pinfunction "IO_25_15_L19") (pintype "bidirectional"))
      (node (ref "IC39") (pin "V24") (pinfunction "IO_L6P_T0_13_V24") (pintype "bidirectional"))
      (node (ref "IC39") (pin "W18") (pinfunction "IO_L19N_T3_VREF_13_W18") (pintype "bidirectional"))
    )
    (net (code "187") (name "unconnected-(IC39A-IO_L13N_T2_MRCC_12-PadAB19)") (class "Default")
      (node (ref "IC39") (pin "AB19") (pinfunction "IO_L13N_T2_MRCC_12_AB19") (pintype "bidirectional+no_connect"))
    )
    (net (code "188") (name "unconnected-(IC39A-IO_L14N_T2_SRCC_12-PadAD19)") (class "Default")
      (node (ref "IC39") (pin "AD19") (pinfunction "IO_L14N_T2_SRCC_12_AD19") (pintype "bidirectional+no_connect"))
    )
    (net (code "189") (name "unconnected-(IC39A-IO_L14P_T2_SRCC_12-PadAC19)") (class "Default")
      (node (ref "IC39") (pin "AC19") (pinfunction "IO_L14P_T2_SRCC_12_AC19") (pintype "bidirectional+no_connect"))
    )
    (net (code "190") (name "unconnected-(IC39A-IO_L23P_T3_12-PadY15)") (class "Default")
      (node (ref "IC39") (pin "Y15") (pinfunction "IO_L23P_T3_12_Y15") (pintype "bidirectional+no_connect"))
    )
    (net (code "191") (name "unconnected-(IC39B-IO_L11P_T1_SRCC_13-PadY22)") (class "Default")
      (node (ref "IC39") (pin "Y22") (pinfunction "IO_L11P_T1_SRCC_13_Y22") (pintype "bidirectional+no_connect"))
    )
    (net (code "192") (name "unconnected-(IC39B-IO_L14N_T2_SRCC_13-PadY21)") (class "Default")
      (node (ref "IC39") (pin "Y21") (pinfunction "IO_L14N_T2_SRCC_13_Y21") (pintype "bidirectional+no_connect"))
    )
    (net (code "193") (name "unconnected-(IC39B-IO_L15N_T2_DQS_13-PadU20)") (class "Default")
      (node (ref "IC39") (pin "U20") (pinfunction "IO_L15N_T2_DQS_13_U20") (pintype "bidirectional+no_connect"))
    )
    (net (code "194") (name "unconnected-(IC39B-IO_L19P_T3_13-PadV18)") (class "Default")
      (node (ref "IC39") (pin "V18") (pinfunction "IO_L19P_T3_13_V18") (pintype "bidirectional+no_connect"))
    )
    (net (code "195") (name "unconnected-(IC39D-IO_L6N_T0_VREF_15-PadM17)") (class "Default")
      (node (ref "IC39") (pin "M17") (pinfunction "IO_L6N_T0_VREF_15_M17") (pintype "bidirectional+no_connect"))
    )
    (net (code "196") (name "unconnected-(IC39D-IO_L11N_T1_SRCC_15-PadG21)") (class "Default")
      (node (ref "IC39") (pin "G21") (pinfunction "IO_L11N_T1_SRCC_15_G21") (pintype "bidirectional+no_connect"))
    )
    (net (code "197") (name "unconnected-(IC39D-IO_L11P_T1_SRCC_15-PadG20)") (class "Default")
      (node (ref "IC39") (pin "G20") (pinfunction "IO_L11P_T1_SRCC_15_G20") (pintype "bidirectional+no_connect"))
    )
    (net (code "198") (name "unconnected-(IC39D-IO_L13N_T2_MRCC_15-PadH22)") (class "Default")
      (node (ref "IC39") (pin "H22") (pinfunction "IO_L13N_T2_MRCC_15_H22") (pintype "bidirectional+no_connect"))
    )
  )
)
